# SCH_Water-Quality-monitoring_2025-07-13.net
KiCad netlist of a schematic drawn in EasyEDA
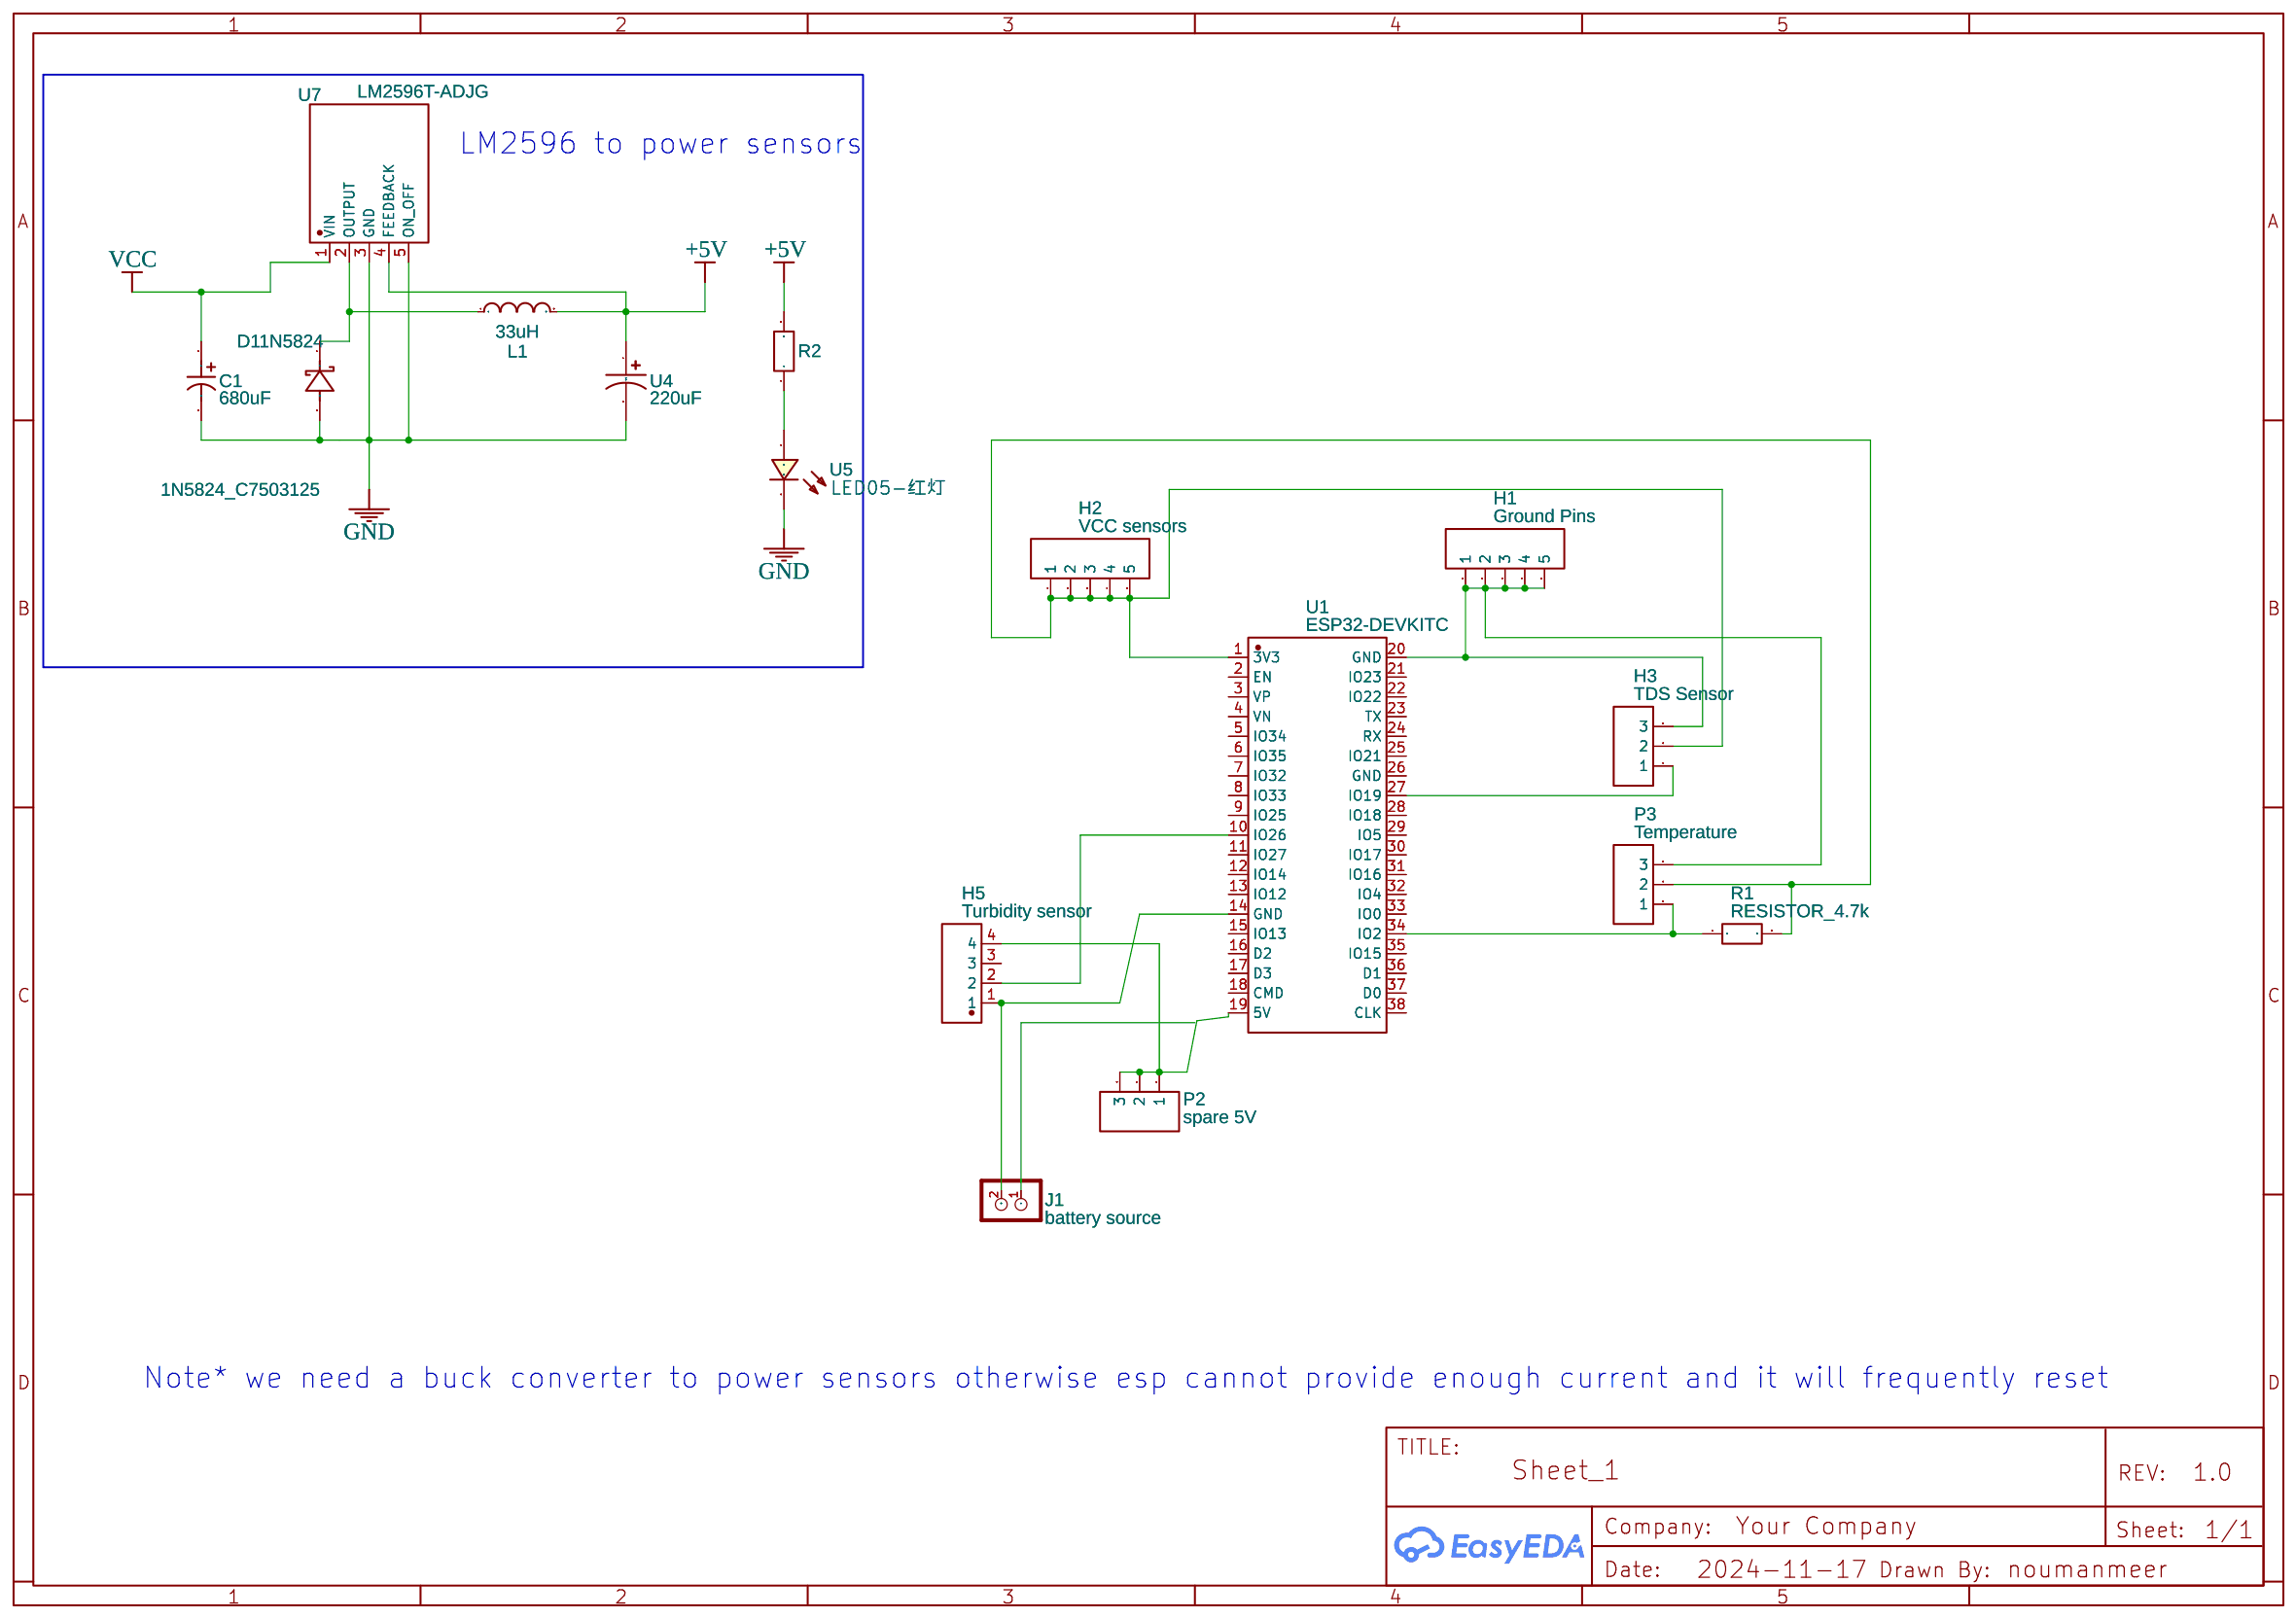
[diagram p0: schematic sheet]

(export (version "E")
  (design (tool "Eeschema 10.0.6"))
  (components
    (comp (ref "C1")
      (value "680uF")
      (fields
        (field (name "Manufacturer Part") "22UF400V87EC0285")
        (field (name "Manufacturer") "KNSCHA(科尼盛)")
      )
      (libsource (lib "") (part "22UF400V87EC0285"))
    )
    (comp (ref "D11N5824")
      (value "1N5824_C7503125")
      (fields (field (name "Manufacturer Part") "1N5824") (field (name "Manufacturer") "FUXINSEMI(富芯森美)"))
      (libsource (lib "") (part "1N5824_C7503125"))
    )
    (comp (ref "H1")
      (value "Ground Pins")
      (fields (field (name "Manufacturer Part") "2.54-1*5P母") (field (name "Manufacturer") "BOOMELE(博穆精密)"))
      (libsource (lib "") (part "Header-Female-2.54_1x5"))
    )
    (comp (ref "H2")
      (value "VCC sensors")
      (fields (field (name "Manufacturer Part") "2.54-1*5P母") (field (name "Manufacturer") "BOOMELE(博穆精密)"))
      (libsource (lib "") (part "Header-Female-2.54_1x5"))
    )
    (comp (ref "H3")
      (value "TDS Sensor")
      (fields (field (name "Manufacturer Part") "2.54-1*3P针") (field (name "Manufacturer") "BOOMELE(博穆精密)"))
      (libsource (lib "") (part "Header-Male-2.54_1x3"))
    )
    (comp (ref "H5")
      (value "Turbidity sensor")
      (fields (field (name "Manufacturer Part") "PM2.54-1*4") (field (name "Manufacturer") "ZHOURI(洲日)"))
      (libsource (lib "") (part "PM2.54-1*4"))
    )
    (comp (ref "J1") (value "battery source") (libsource (lib "") (part "CON_TERMINAL_BLOCK_02-5MM")))
    (comp (ref "L1")
      (value "33uH")
      (fields (field (name "Manufacturer Part") "CKCS5040-33uH/M") (field (name "Manufacturer") "CENKER(岑科)"))
      (libsource (lib "") (part "CKCS5040-33UH/M"))
    )
    (comp (ref "P2")
      (value "spare 5V")
      (fields (field (name "Manufacturer Part") "2.54-1*3P母") (field (name "Manufacturer") "BOOMELE(博穆精密)"))
      (libsource (lib "") (part "Header-Female-2.54_1x3_1"))
    )
    (comp (ref "P3")
      (value "Temperature")
      (fields (field (name "Manufacturer Part") "2.54-1*3P母") (field (name "Manufacturer") "BOOMELE(博穆精密)"))
      (libsource (lib "") (part "Header-Female-2.54_1x3"))
    )
    (comp (ref "R1")
      (value "RESISTOR_4.7k")
      (fields
        (field (name "Manufacturer Part") "Resistor_THT:R_Axial_DIN0309_L9.0mm_D3.2mm_P2.54mm_Vertical")
      )
      (libsource (lib "") (part "RESISTOR_THT{colon}R_AXIAL_DIN0309_L9.0MM_D3.2MM_P2.54MM_VERTICAL"))
    )
    (comp (ref "R2")
      (value "贴片电阻CHIPRESISTORS")
      (fields (field (name "Manufacturer Part") "贴片电阻ChipResistors"))
      (libsource (lib "") (part "贴片电阻CHIPRESISTORS"))
    )
    (comp (ref "U1")
      (value "ESP32-DEVKITC")
      (fields
        (field (name "Manufacturer Part") "ESP32-DevKitC")
        (field (name "Manufacturer") "ESPRESSIF(乐鑫)")
      )
      (libsource (lib "") (part "ESP32-DEVKITC"))
    )
    (comp (ref "U4")
      (value "220uF")
      (fields
        (field (name "Manufacturer Part") "16YK220M6.3X11")
        (field (name "Manufacturer") "rubycon(红宝石)")
      )
      (libsource (lib "") (part "16YK220M6.3X11"))
    )
    (comp (ref "U5") (value "LED05-红灯") (libsource (lib "") (part "LED05-红灯")))
    (comp (ref "U7")
      (value "LM2596T-ADJG")
      (fields (field (name "Manufacturer") "HGC(深圳汉芯)"))
      (libsource (lib "") (part "LM2596T-ADJG"))
    )
  )
  (nets
    (net (code "1") (name "+5V") (class "Default")
      (node (ref "L1") (pin "2") (pinfunction "2_2") (pintype "unspecified"))
      (node (ref "R2") (pin "2") (pinfunction "2_2") (pintype "unspecified"))
      (node (ref "U4") (pin "1") (pinfunction "1_1") (pintype "unspecified"))
      (node (ref "U7") (pin "4") (pinfunction "FEEDBACK_4") (pintype "unspecified"))
    )
    (net (code "2") (name "GND") (class "Default")
      (node (ref "C1") (pin "2") (pinfunction "2_2") (pintype "input"))
      (node (ref "D11N5824") (pin "2") (pinfunction "A_2") (pintype "unspecified"))
      (node (ref "U4") (pin "2") (pinfunction "2_2") (pintype "unspecified"))
      (node (ref "U5") (pin "2") (pinfunction "2_2") (pintype "unspecified"))
      (node (ref "U7") (pin "3") (pinfunction "GND_3") (pintype "unspecified"))
      (node (ref "U7") (pin "5") (pinfunction "ON_OFF_5") (pintype "unspecified"))
    )
    (net (code "3") (name "Net-(D11N5824-K)") (class "Default")
      (node (ref "D11N5824") (pin "1") (pinfunction "K_1") (pintype "unspecified"))
      (node (ref "L1") (pin "1") (pinfunction "1_1") (pintype "unspecified"))
      (node (ref "U7") (pin "2") (pinfunction "OUTPUT_2") (pintype "unspecified"))
    )
    (net (code "4") (name "Net-(H1-Pad1)") (class "Default")
      (node (ref "H1") (pin "1") (pinfunction "1_1") (pintype "input"))
      (node (ref "H1") (pin "2") (pinfunction "2_2") (pintype "input"))
      (node (ref "H1") (pin "3") (pinfunction "3_3") (pintype "input"))
      (node (ref "H1") (pin "4") (pinfunction "4_4") (pintype "input"))
      (node (ref "H1") (pin "5") (pinfunction "5_5") (pintype "input"))
      (node (ref "H3") (pin "3") (pinfunction "3_3") (pintype "input"))
      (node (ref "P3") (pin "3") (pinfunction "3_3") (pintype "input"))
      (node (ref "U1") (pin "20") (pinfunction "GND_20") (pintype "unspecified"))
    )
    (net (code "5") (name "Net-(H5-Pad1)") (class "Default")
      (node (ref "H5") (pin "1") (pinfunction "1_1") (pintype "unspecified"))
      (node (ref "J1") (pin "2") (pinfunction "2_2") (pintype "unspecified"))
      (node (ref "U1") (pin "14") (pinfunction "GND_14") (pintype "unspecified"))
    )
    (net (code "6") (name "Net-(R2-Pad1)") (class "Default")
      (node (ref "R2") (pin "1") (pinfunction "1_1") (pintype "unspecified"))
      (node (ref "U5") (pin "1") (pinfunction "1_1") (pintype "unspecified"))
    )
    (net (code "7") (name "Net-(U1-3V3)") (class "Default")
      (node (ref "H2") (pin "1") (pinfunction "1_1") (pintype "input"))
      (node (ref "H2") (pin "2") (pinfunction "2_2") (pintype "input"))
      (node (ref "H2") (pin "3") (pinfunction "3_3") (pintype "input"))
      (node (ref "H2") (pin "4") (pinfunction "4_4") (pintype "input"))
      (node (ref "H2") (pin "5") (pinfunction "5_5") (pintype "input"))
      (node (ref "H3") (pin "2") (pinfunction "2_2") (pintype "input"))
      (node (ref "P3") (pin "2") (pinfunction "2_2") (pintype "input"))
      (node (ref "R1") (pin "2") (pinfunction "2_2") (pintype "unspecified"))
      (node (ref "U1") (pin "1") (pinfunction "3V3_1") (pintype "unspecified"))
    )
    (net (code "8") (name "Net-(U1-5V)") (class "Default")
      (node (ref "H5") (pin "4") (pinfunction "4_4") (pintype "unspecified"))
      (node (ref "P2") (pin "1") (pinfunction "1_1") (pintype "input"))
      (node (ref "P2") (pin "2") (pinfunction "2_2") (pintype "input"))
      (node (ref "P2") (pin "3") (pinfunction "3_3") (pintype "input"))
      (node (ref "U1") (pin "19") (pinfunction "5V_19") (pintype "unspecified"))
    )
    (net (code "9") (name "Net-(U1-IO2)") (class "Default")
      (node (ref "P3") (pin "1") (pinfunction "1_1") (pintype "input"))
      (node (ref "R1") (pin "1") (pinfunction "1_1") (pintype "unspecified"))
      (node (ref "U1") (pin "34") (pinfunction "IO2_34") (pintype "unspecified"))
    )
    (net (code "10") (name "Net-(U1-IO19)") (class "Default")
      (node (ref "H3") (pin "1") (pinfunction "1_1") (pintype "input"))
      (node (ref "U1") (pin "27") (pinfunction "IO19_27") (pintype "unspecified"))
    )
    (net (code "11") (name "Net-(U1-IO26)") (class "Default")
      (node (ref "H5") (pin "2") (pinfunction "2_2") (pintype "unspecified"))
      (node (ref "U1") (pin "10") (pinfunction "IO26_10") (pintype "unspecified"))
    )
    (net (code "12") (name "VCC") (class "Default")
      (node (ref "C1") (pin "1") (pinfunction "1_1") (pintype "input"))
      (node (ref "U7") (pin "1") (pinfunction "VIN_1") (pintype "unspecified"))
    )
    (net (code "13") (name "unconnected-(H5-Pad3)") (class "Default")
      (node (ref "H5") (pin "3") (pinfunction "3_3") (pintype "unspecified"))
    )
    (net (code "14") (name "unconnected-(J1-Pad1)") (class "Default")
      (node (ref "J1") (pin "1") (pinfunction "1_1") (pintype "unspecified"))
    )
    (net (code "15") (name "unconnected-(U1-CLK-Pad38)") (class "Default")
      (node (ref "U1") (pin "38") (pinfunction "CLK_38") (pintype "unspecified"))
    )
    (net (code "16") (name "unconnected-(U1-CMD-Pad18)") (class "Default")
      (node (ref "U1") (pin "18") (pinfunction "CMD_18") (pintype "unspecified"))
    )
    (net (code "17") (name "unconnected-(U1-D0-Pad37)") (class "Default")
      (node (ref "U1") (pin "37") (pinfunction "D0_37") (pintype "unspecified"))
    )
    (net (code "18") (name "unconnected-(U1-D1-Pad36)") (class "Default")
      (node (ref "U1") (pin "36") (pinfunction "D1_36") (pintype "unspecified"))
    )
    (net (code "19") (name "unconnected-(U1-D2-Pad16)") (class "Default")
      (node (ref "U1") (pin "16") (pinfunction "D2_16") (pintype "unspecified"))
    )
    (net (code "20") (name "unconnected-(U1-D3-Pad17)") (class "Default")
      (node (ref "U1") (pin "17") (pinfunction "D3_17") (pintype "unspecified"))
    )
    (net (code "21") (name "unconnected-(U1-EN-Pad2)") (class "Default")
      (node (ref "U1") (pin "2") (pinfunction "EN_2") (pintype "unspecified"))
    )
    (net (code "22") (name "unconnected-(U1-GND-Pad26)") (class "Default")
      (node (ref "U1") (pin "26") (pinfunction "GND_26") (pintype "unspecified"))
    )
    (net (code "23") (name "unconnected-(U1-IO0-Pad33)") (class "Default")
      (node (ref "U1") (pin "33") (pinfunction "IO0_33") (pintype "unspecified"))
    )
    (net (code "24") (name "unconnected-(U1-IO4-Pad32)") (class "Default")
      (node (ref "U1") (pin "32") (pinfunction "IO4_32") (pintype "unspecified"))
    )
    (net (code "25") (name "unconnected-(U1-IO5-Pad29)") (class "Default")
      (node (ref "U1") (pin "29") (pinfunction "IO5_29") (pintype "unspecified"))
    )
    (net (code "26") (name "unconnected-(U1-IO12-Pad13)") (class "Default")
      (node (ref "U1") (pin "13") (pinfunction "IO12_13") (pintype "unspecified"))
    )
    (net (code "27") (name "unconnected-(U1-IO13-Pad15)") (class "Default")
      (node (ref "U1") (pin "15") (pinfunction "IO13_15") (pintype "unspecified"))
    )
    (net (code "28") (name "unconnected-(U1-IO14-Pad12)") (class "Default")
      (node (ref "U1") (pin "12") (pinfunction "IO14_12") (pintype "unspecified"))
    )
    (net (code "29") (name "unconnected-(U1-IO15-Pad35)") (class "Default")
      (node (ref "U1") (pin "35") (pinfunction "IO15_35") (pintype "unspecified"))
    )
    (net (code "30") (name "unconnected-(U1-IO16-Pad31)") (class "Default")
      (node (ref "U1") (pin "31") (pinfunction "IO16_31") (pintype "unspecified"))
    )
    (net (code "31") (name "unconnected-(U1-IO17-Pad30)") (class "Default")
      (node (ref "U1") (pin "30") (pinfunction "IO17_30") (pintype "unspecified"))
    )
    (net (code "32") (name "unconnected-(U1-IO18-Pad28)") (class "Default")
      (node (ref "U1") (pin "28") (pinfunction "IO18_28") (pintype "unspecified"))
    )
    (net (code "33") (name "unconnected-(U1-IO21-Pad25)") (class "Default")
      (node (ref "U1") (pin "25") (pinfunction "IO21_25") (pintype "unspecified"))
    )
    (net (code "34") (name "unconnected-(U1-IO22-Pad22)") (class "Default")
      (node (ref "U1") (pin "22") (pinfunction "IO22_22") (pintype "unspecified"))
    )
    (net (code "35") (name "unconnected-(U1-IO23-Pad21)") (class "Default")
      (node (ref "U1") (pin "21") (pinfunction "IO23_21") (pintype "unspecified"))
    )
    (net (code "36") (name "unconnected-(U1-IO25-Pad9)") (class "Default")
      (node (ref "U1") (pin "9") (pinfunction "IO25_9") (pintype "unspecified"))
    )
    (net (code "37") (name "unconnected-(U1-IO27-Pad11)") (class "Default")
      (node (ref "U1") (pin "11") (pinfunction "IO27_11") (pintype "unspecified"))
    )
    (net (code "38") (name "unconnected-(U1-IO32-Pad7)") (class "Default")
      (node (ref "U1") (pin "7") (pinfunction "IO32_7") (pintype "unspecified"))
    )
    (net (code "39") (name "unconnected-(U1-IO33-Pad8)") (class "Default")
      (node (ref "U1") (pin "8") (pinfunction "IO33_8") (pintype "unspecified"))
    )
    (net (code "40") (name "unconnected-(U1-IO34-Pad5)") (class "Default")
      (node (ref "U1") (pin "5") (pinfunction "IO34_5") (pintype "unspecified"))
    )
    (net (code "41") (name "unconnected-(U1-IO35-Pad6)") (class "Default")
      (node (ref "U1") (pin "6") (pinfunction "IO35_6") (pintype "unspecified"))
    )
    (net (code "42") (name "unconnected-(U1-RX-Pad24)") (class "Default")
      (node (ref "U1") (pin "24") (pinfunction "RX_24") (pintype "unspecified"))
    )
    (net (code "43") (name "unconnected-(U1-TX-Pad23)") (class "Default")
      (node (ref "U1") (pin "23") (pinfunction "TX_23") (pintype "unspecified"))
    )
    (net (code "44") (name "unconnected-(U1-VN-Pad4)") (class "Default")
      (node (ref "U1") (pin "4") (pinfunction "VN_4") (pintype "unspecified"))
    )
    (net (code "45") (name "unconnected-(U1-VP-Pad3)") (class "Default")
      (node (ref "U1") (pin "3") (pinfunction "VP_3") (pintype "unspecified"))
    )
  )
)
